# Rotary_Encoder_Breakout.net
KiCad netlist of a schematic drawn in EAGLE
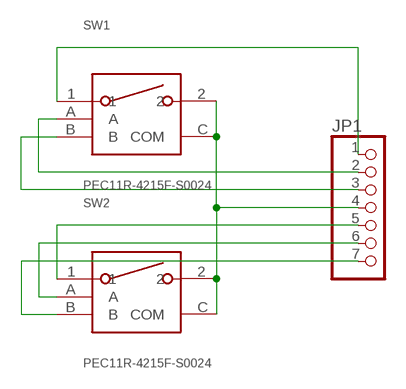
[diagram p0: schematic, sheet 1]

(export (version "E")
  (design (tool "Eeschema 10.0.6"))
  (components
    (comp (ref "JP1")
      (value "PINHD-1X07_2.54-90°")
      (footprint "eagle-import:1X07_90")
      (libsource (lib "eagle-import") (part "PINHD-1X07_2.54-90°"))
    )
    (comp (ref "SW1")
      (value "PEC11R-4215F-S0024")
      (footprint "eagle-import:PEC11R-4215F-S0024")
      (fields
        (field (name "DIGIKEY_PART_NUMBER") "PEC11R-4215F-S0024-ND")
        (field (name "MANUFACTURER") "Bourns Inc.")
        (field (name "CREATED_BY") "PCBLayout.com")
      )
      (libsource (lib "eagle-import") (part "PEC11R-4215F-S0024"))
    )
    (comp (ref "SW2")
      (value "PEC11R-4215F-S0024")
      (footprint "eagle-import:PEC11R-4215F-S0024")
      (fields
        (field (name "DIGIKEY_PART_NUMBER") "PEC11R-4215F-S0024-ND")
        (field (name "MANUFACTURER") "Bourns Inc.")
        (field (name "CREATED_BY") "PCBLayout.com")
      )
      (libsource (lib "eagle-import") (part "PEC11R-4215F-S0024"))
    )
  )
  (nets
    (net (code "1") (name "Net-(JP1-Pad1)") (class "Default")
      (node (ref "JP1") (pin "1") (pinfunction "1_1") (pintype "passive"))
      (node (ref "SW1") (pin "1") (pinfunction "1_1") (pintype "passive"))
    )
    (net (code "2") (name "Net-(JP1-Pad2)") (class "Default")
      (node (ref "JP1") (pin "2") (pinfunction "2_2") (pintype "passive"))
      (node (ref "SW1") (pin "A") (pinfunction "A_A") (pintype "passive"))
    )
    (net (code "3") (name "Net-(JP1-Pad3)") (class "Default")
      (node (ref "JP1") (pin "3") (pinfunction "3_3") (pintype "passive"))
      (node (ref "SW1") (pin "B") (pinfunction "B_B") (pintype "passive"))
    )
    (net (code "4") (name "Net-(JP1-Pad5)") (class "Default")
      (node (ref "JP1") (pin "5") (pinfunction "5_5") (pintype "passive"))
      (node (ref "SW2") (pin "1") (pinfunction "1_1") (pintype "passive"))
    )
    (net (code "5") (name "Net-(JP1-Pad6)") (class "Default")
      (node (ref "JP1") (pin "6") (pinfunction "6_6") (pintype "passive"))
      (node (ref "SW2") (pin "A") (pinfunction "A_A") (pintype "passive"))
    )
    (net (code "6") (name "Net-(JP1-Pad7)") (class "Default")
      (node (ref "JP1") (pin "7") (pinfunction "7_7") (pintype "passive"))
      (node (ref "SW2") (pin "B") (pinfunction "B_B") (pintype "passive"))
    )
    (net (code "7") (name "Net-(SW1-COM)") (class "Default")
      (node (ref "JP1") (pin "4") (pinfunction "4_4") (pintype "passive"))
      (node (ref "SW1") (pin "2") (pinfunction "2_2") (pintype "passive"))
      (node (ref "SW1") (pin "C") (pinfunction "COM_C") (pintype "passive"))
      (node (ref "SW2") (pin "2") (pinfunction "2_2") (pintype "passive"))
      (node (ref "SW2") (pin "C") (pinfunction "COM_C") (pintype "passive"))
    )
  )
)
